# USB.net
KiCad netlist of a schematic drawn in Altium Designer
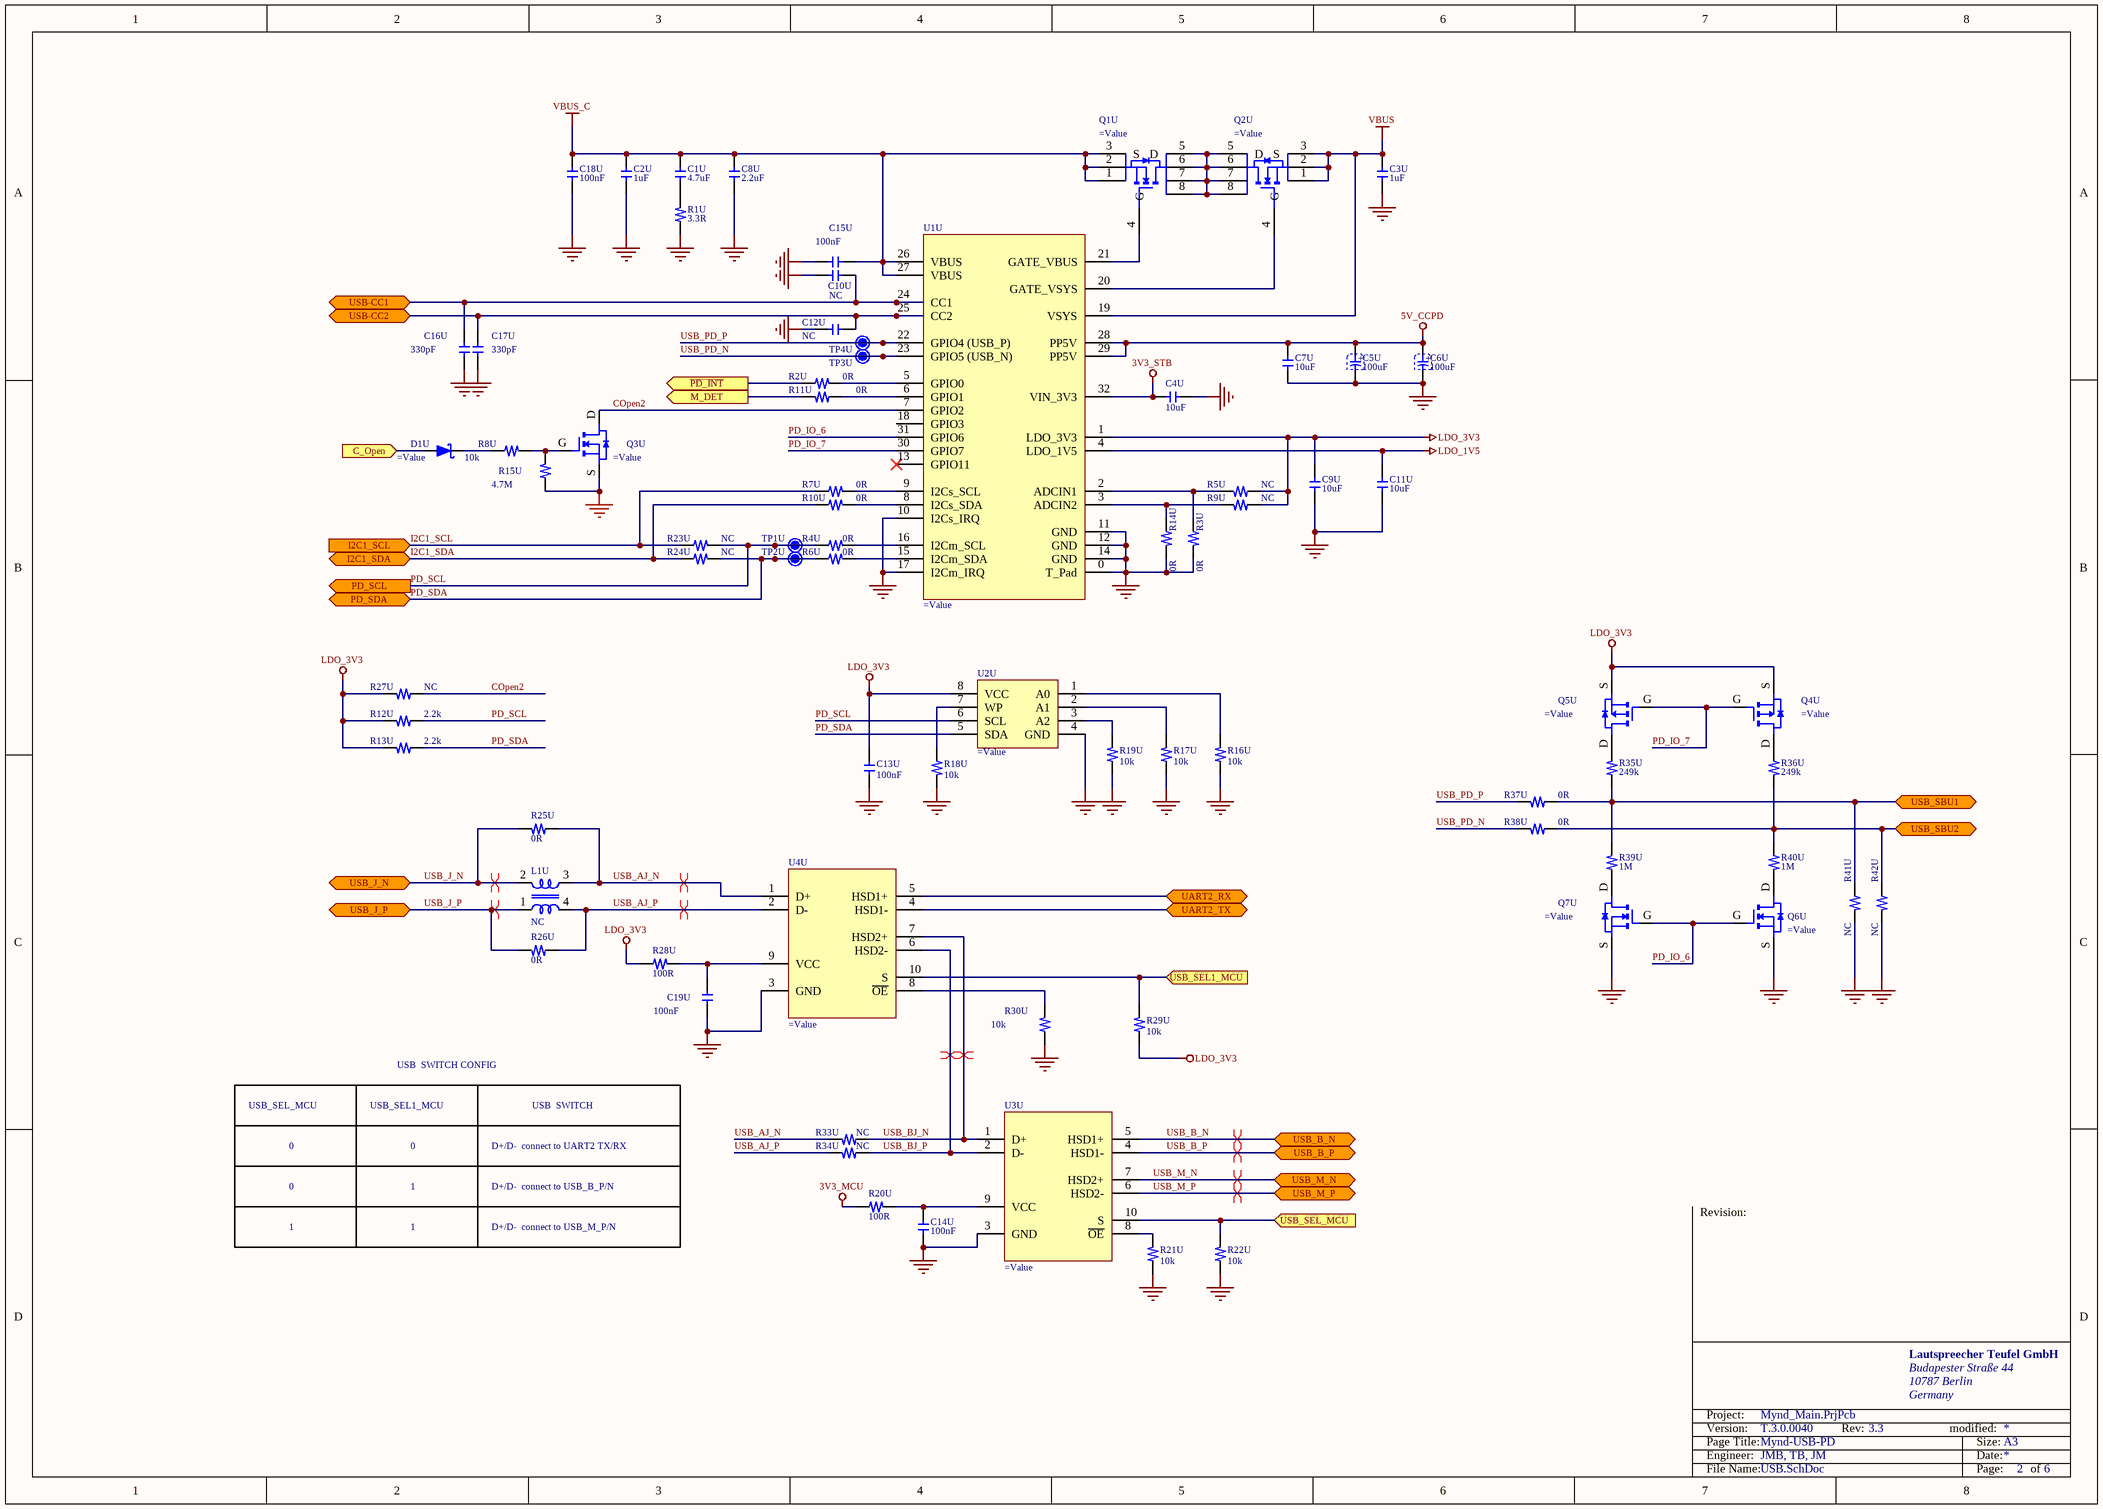
[diagram p0: USB.SchDoc]

(export (version "E")
  (design (tool "Eeschema 10.0.6"))
  (components
    (comp (ref "C1U")
      (value "4.7uF")
      (footprint "C0805_145")
      (description "PSHF SMD M CAP 4.7uF 25V ±10% 0805 X7R")
      (fields (field (name "MANUFACTURER") "Multi Sourced") (field (name "TOLERANCE") "±10%"))
      (libsource (lib "altium-import") (part "root_3_CAP1_"))
    )
    (comp (ref "C2U")
      (value "1uF")
      (footprint "C0805_145")
      (description "PSHF SMD M CAP 1uF 50V ±10% 0805 X7R")
      (fields (field (name "MANUFACTURER") "Multi Sourced") (field (name "TOLERANCE") "±10%"))
      (libsource (lib "altium-import") (part "root_3_CAP1_"))
    )
    (comp (ref "C3U")
      (value "1uF")
      (footprint "C0805_145")
      (description "PSHF SMD M CAP 1uF 50V ±10% 0805 X7R")
      (fields (field (name "MANUFACTURER") "Multi Sourced") (field (name "TOLERANCE") "±10%"))
      (libsource (lib "altium-import") (part "root_3_CAP1_"))
    )
    (comp (ref "C4U")
      (value "10uF")
      (footprint "C0805_145")
      (description "PSHF SMD M CAP 10uF 16V ±10% 0805 X7R")
      (fields (field (name "MANUFACTURER") "Multi Sourced") (field (name "TOLERANCE") "±10%"))
      (libsource (lib "altium-import") (part "root_2_CAP1_"))
    )
    (comp (ref "C5U")
      (value "100uF")
      (footprint "ECAP_SMD_630X540")
      (description "PS SMD COND ELECT 100uF 16V ±20% 105℃")
      (fields (field (name "MANUFACTURER") "Multi Sourced") (field (name "TOLERANCE") "±20%"))
      (libsource (lib "altium-import") (part "root_3_ECAP2_"))
    )
    (comp (ref "C6U")
      (value "100uF")
      (footprint "ECAP_SMD_630X540")
      (description "PS SMD COND ELECT 100uF 16V ±20% 105℃")
      (fields (field (name "MANUFACTURER") "Multi Sourced") (field (name "TOLERANCE") "±20%"))
      (libsource (lib "altium-import") (part "root_3_ECAP2_"))
    )
    (comp (ref "C7U")
      (value "10uF")
      (footprint "C0805_145")
      (description "PSHF SMD M CAP 10uF 16V ±10% 0805 X7R")
      (fields (field (name "MANUFACTURER") "Multi Sourced") (field (name "TOLERANCE") "±10%"))
      (libsource (lib "altium-import") (part "root_1_CAP1_"))
    )
    (comp (ref "C8U")
      (value "2.2uF")
      (footprint "C0805_145")
      (description "GPHF $ SMD M CAP 2.2uF 50V ±10% 0805 X5R")
      (fields (field (name "MANUFACTURER") "Multi Sourced") (field (name "TOLERANCE") "±10%"))
      (libsource (lib "altium-import") (part "root_3_CAP1_"))
    )
    (comp (ref "C9U")
      (value "10uF")
      (footprint "C0805_145")
      (description "PSHF SMD M CAP 10uF 16V ±10% 0805 X7R")
      (fields (field (name "MANUFACTURER") "Multi Sourced") (field (name "TOLERANCE") "±10%"))
      (libsource (lib "altium-import") (part "root_1_CAP1_"))
    )
    (comp (ref "C10U")
      (value "330pF")
      (footprint "C0603X80")
      (description "PSHF SMD M CAP 330pF 50V ±10% 0603 X7R")
      (fields (field (name "MANUFACTURER") "Multi Sourced") (field (name "TOLERANCE") "±10%"))
      (libsource (lib "altium-import") (part "root_2_CAP1_"))
    )
    (comp (ref "C11U")
      (value "10uF")
      (footprint "C0805_145")
      (description "PSHF SMD M CAP 10uF 16V ±10% 0805 X7R")
      (fields (field (name "MANUFACTURER") "Multi Sourced") (field (name "TOLERANCE") "±10%"))
      (libsource (lib "altium-import") (part "root_1_CAP1_"))
    )
    (comp (ref "C12U")
      (value "330pF")
      (footprint "C0603X80")
      (description "PSHF SMD M CAP 330pF 50V ±10% 0603 X7R")
      (fields (field (name "MANUFACTURER") "Multi Sourced") (field (name "TOLERANCE") "±10%"))
      (libsource (lib "altium-import") (part "root_2_CAP1_"))
    )
    (comp (ref "C13U")
      (value "100nF")
      (footprint "C0603X100")
      (description "PSHF SMD M CAP 100nF 25V ±10% 0603 X7R")
      (fields (field (name "MANUFACTURER") "Multi Sourced") (field (name "TOLERANCE") "±10%"))
      (libsource (lib "altium-import") (part "root_3_mirrored_CAP1_"))
    )
    (comp (ref "C14U")
      (value "100nF")
      (footprint "C0603X100")
      (description "PSHF SMD M CAP 100nF 25V ±10% 0603 X7R")
      (fields (field (name "MANUFACTURER") "Multi Sourced") (field (name "TOLERANCE") "±10%"))
      (libsource (lib "altium-import") (part "root_3_mirrored_CAP1_"))
    )
    (comp (ref "C15U")
      (value "100nF")
      (footprint "C0603X105")
      (description "GPHF SMD M CAP 100nF 50V ±5% 0603 X7R")
      (fields (field (name "MANUFACTURER") "Multi Sourced") (field (name "TOLERANCE") "±5%"))
      (libsource (lib "altium-import") (part "root_2_CAP1_"))
    )
    (comp (ref "C16U")
      (value "330pF")
      (footprint "C0603X80")
      (description "GPHF SMD M CAP 330pF 50V ±5% 0603 NPO")
      (fields (field (name "MANUFACTURER") "Multi Sourced") (field (name "TOLERANCE") "±5%"))
      (libsource (lib "altium-import") (part "root_3_CAP1_"))
    )
    (comp (ref "C17U")
      (value "330pF")
      (footprint "C0603X80")
      (description "GPHF SMD M CAP 330pF 50V ±5% 0603 NPO")
      (fields (field (name "MANUFACTURER") "Multi Sourced") (field (name "TOLERANCE") "±5%"))
      (libsource (lib "altium-import") (part "root_3_CAP1_"))
    )
    (comp (ref "C18U")
      (value "100nF")
      (footprint "C0603X105")
      (description "GPHF SMD M CAP 100nF 50V ±5% 0603 X7R")
      (fields (field (name "MANUFACTURER") "Multi Sourced") (field (name "TOLERANCE") "±5%"))
      (libsource (lib "altium-import") (part "root_3_CAP1_"))
    )
    (comp (ref "C19U")
      (value "100nF")
      (footprint "C0603X100")
      (description "PSHF SMD M CAP 100nF 25V ±10% 0603 X7R")
      (fields (field (name "MANUFACTURER") "Multi Sourced") (field (name "TOLERANCE") "±10%"))
      (libsource (lib "altium-import") (part "root_3_mirrored_CAP1_"))
    )
    (comp (ref "D1U")
      (value "~")
      (footprint "SOD-323")
      (description "GP SMD DIODE 2P 30V SOD323 BAT54WS PANJIT")
      (fields (field (name "MANUFACTURER") "PANJIT") (field (name "VOLTAGE") "30V"))
      (libsource (lib "altium-import") (part "root_2_mirrored_DIODE_SCHOTTKY1_"))
    )
    (comp (ref "L1U")
      (value "NC")
      (footprint "CET2012D")
      (description "COMMON MODE COIL 90Ohm 100MHz 400mA")
      (fields (field (name "MANUFACTURER") "CET CHAMPI") (field (name "PART_NUMBER") "CET2012A-900S"))
      (libsource (lib "altium-import") (part "root_2_mirrored_CET9070F-701_"))
    )
    (comp (ref "Q1U")
      (value "~")
      (footprint "DFN8_500X600X100_127_A")
      (description "PS SMD FET 8P DFN8 AP4024GEMT-HF APEC")
      (fields (field (name "MANUFACTURER") "[APEC]") (field (name "VOLTAGE") "30V"))
      (libsource (lib "altium-import") (part "root_1_mirrored_N-MOS2_8Pin_"))
    )
    (comp (ref "Q2U")
      (value "~")
      (footprint "DFN8_500X600X100_127_A")
      (description "PS SMD FET 8P DFN8 AP4024GEMT-HF APEC")
      (fields (field (name "MANUFACTURER") "[APEC]") (field (name "VOLTAGE") "30V"))
      (libsource (lib "altium-import") (part "root_1_N-MOS2_8Pin_"))
    )
    (comp (ref "Q3U")
      (value "~")
      (footprint "SOT23-GSD")
      (description "GP SMD FET 3P SOT23 2N7002K CTE")
      (fields (field (name "MANUFACTURER") "CTE") (field (name "VOLTAGE") "60V"))
      (libsource (lib "altium-import") (part "root_0_N-MOS1_"))
    )
    (comp (ref "Q4U")
      (value "~")
      (footprint "SOT23-GSD")
      (description "GPHF SMD FET 3P -30V SOT-23 CJ3401 CJ")
      (fields (field (name "MANUFACTURER") "CJ") (field (name "VOLTAGE") "-30"))
      (libsource (lib "altium-import") (part "root_2_mirrored_P-MOS1_"))
    )
    (comp (ref "Q5U")
      (value "~")
      (footprint "SOT23-GSD")
      (description "GPHF SMD FET 3P -30V SOT-23 CJ3401 CJ")
      (fields (field (name "MANUFACTURER") "CJ") (field (name "VOLTAGE") "-30"))
      (libsource (lib "altium-import") (part "root_2_P-MOS1_"))
    )
    (comp (ref "Q6U")
      (value "~")
      (footprint "SOT23_16_GSD")
      (description "GP FET 3P AO3402 SOT23 ALPHA 30V/4A")
      (fields (field (name "MANUFACTURER") "AOS") (field (name "VOLTAGE") "30V"))
      (libsource (lib "altium-import") (part "root_0_N-MOS1_"))
    )
    (comp (ref "Q7U")
      (value "~")
      (footprint "SOT23_16_GSD")
      (description "GP FET 3P AO3402 SOT23 ALPHA 30V/4A")
      (fields (field (name "MANUFACTURER") "AOS") (field (name "VOLTAGE") "30V"))
      (libsource (lib "altium-import") (part "root_0_mirrored_N-MOS1_"))
    )
    (comp (ref "R1U")
      (value "3.3R")
      (footprint "R0603")
      (description "PS SMD RES. 3.3OHM 1/10W 1% 0603")
      (fields (field (name "TOLERANCE") "1%") (field (name "MANUFACTURER") "Multi-Sourced"))
      (libsource (lib "altium-import") (part "root_1_mirrored_RES1_"))
    )
    (comp (ref "R2U")
      (value "0R")
      (footprint "R0603")
      (description "PS SMD RES. 0OHM 1/10W 5% 0603")
      (fields (field (name "TOLERANCE") "1%") (field (name "MANUFACTURER") "Multi-Sourced"))
      (libsource (lib "altium-import") (part "root_2_mirrored_RES1_"))
    )
    (comp (ref "R3U")
      (value "0R")
      (footprint "R0603")
      (description "GPHF SMD RES. 0OHM 1/10W 5% 0603")
      (fields (field (name "TOLERANCE") "5%") (field (name "MANUFACTURER") "Multi-Sourced"))
      (libsource (lib "altium-import") (part "root_3_mirrored_RES1_"))
    )
    (comp (ref "R4U")
      (value "0R")
      (footprint "R0603")
      (description "PS SMD RES. 0OHM 1/10W 5% 0603")
      (fields (field (name "TOLERANCE") "1%") (field (name "MANUFACTURER") "Multi-Sourced"))
      (libsource (lib "altium-import") (part "root_2_mirrored_RES1_"))
    )
    (comp (ref "R5U")
      (value "13k")
      (footprint "R0603")
      (description "GPHF SMD RES. 13KOHM 1/10W 1% 0603")
      (fields (field (name "TOLERANCE") "1%") (field (name "MANUFACTURER") "Multi-Sourced"))
      (libsource (lib "altium-import") (part "root_0_mirrored_RES1_"))
    )
    (comp (ref "R6U")
      (value "0R")
      (footprint "R0603")
      (description "PS SMD RES. 0OHM 1/10W 5% 0603")
      (fields (field (name "TOLERANCE") "1%") (field (name "MANUFACTURER") "Multi-Sourced"))
      (libsource (lib "altium-import") (part "root_2_mirrored_RES1_"))
    )
    (comp (ref "R7U")
      (value "0R")
      (footprint "R0603")
      (description "PS SMD RES. 0OHM 1/10W 5% 0603")
      (fields (field (name "TOLERANCE") "1%") (field (name "MANUFACTURER") "Multi-Sourced"))
      (libsource (lib "altium-import") (part "root_2_mirrored_RES1_"))
    )
    (comp (ref "R8U")
      (value "10k")
      (footprint "R0603")
      (description "GPHF SMD RES. 10KOHM 1/10W 5% 0603")
      (fields (field (name "TOLERANCE") "5%") (field (name "MANUFACTURER") "Multi-Sourced"))
      (libsource (lib "altium-import") (part "root_2_mirrored_RES1_"))
    )
    (comp (ref "R9U")
      (value "13k")
      (footprint "R0603")
      (description "GPHF SMD RES. 13KOHM 1/10W 1% 0603")
      (fields (field (name "TOLERANCE") "1%") (field (name "MANUFACTURER") "Multi-Sourced"))
      (libsource (lib "altium-import") (part "root_0_mirrored_RES1_"))
    )
    (comp (ref "R10U")
      (value "0R")
      (footprint "R0603")
      (description "PS SMD RES. 0OHM 1/10W 5% 0603")
      (fields (field (name "TOLERANCE") "1%") (field (name "MANUFACTURER") "Multi-Sourced"))
      (libsource (lib "altium-import") (part "root_2_mirrored_RES1_"))
    )
    (comp (ref "R11U")
      (value "0R")
      (footprint "R0603")
      (description "PS SMD RES. 0OHM 1/10W 5% 0603")
      (fields (field (name "TOLERANCE") "1%") (field (name "MANUFACTURER") "Multi-Sourced"))
      (libsource (lib "altium-import") (part "root_0_mirrored_RES1_"))
    )
    (comp (ref "R12U")
      (value "2.2k")
      (footprint "R0603")
      (description "PS SMD RES. 2.2KOHM 1/10W 1% 0603")
      (fields (field (name "TOLERANCE") "1%") (field (name "MANUFACTURER") "Multi-Sourced"))
      (libsource (lib "altium-import") (part "root_0_mirrored_RES1_"))
    )
    (comp (ref "R13U")
      (value "2.2k")
      (footprint "R0603")
      (description "PS SMD RES. 2.2KOHM 1/10W 1% 0603")
      (fields (field (name "TOLERANCE") "1%") (field (name "MANUFACTURER") "Multi-Sourced"))
      (libsource (lib "altium-import") (part "root_0_mirrored_RES1_"))
    )
    (comp (ref "R14U")
      (value "0R")
      (footprint "R0603")
      (description "GPHF SMD RES. 0OHM 1/10W 5% 0603")
      (fields (field (name "TOLERANCE") "5%") (field (name "MANUFACTURER") "Multi-Sourced"))
      (libsource (lib "altium-import") (part "root_3_mirrored_RES1_"))
    )
    (comp (ref "R15U")
      (value "4.7M")
      (footprint "R0603")
      (description "PS SMD RES. 4.7MOHM 1/10W 5% 0603")
      (fields (field (name "TOLERANCE") "5%") (field (name "MANUFACTURER") "Multi-Sourced"))
      (libsource (lib "altium-import") (part "root_3_RES1_"))
    )
    (comp (ref "R16U")
      (value "10k")
      (footprint "R0603")
      (description "PS SMD RES. 10KOHM 1/10W 1% 0603")
      (fields (field (name "TOLERANCE") "1%") (field (name "MANUFACTURER") "Multi-Sourced"))
      (libsource (lib "altium-import") (part "root_3_RES1_"))
    )
    (comp (ref "R17U")
      (value "10k")
      (footprint "R0603")
      (description "PS SMD RES. 10KOHM 1/10W 1% 0603")
      (fields (field (name "TOLERANCE") "1%") (field (name "MANUFACTURER") "Multi-Sourced"))
      (libsource (lib "altium-import") (part "root_3_RES1_"))
    )
    (comp (ref "R18U")
      (value "10k")
      (footprint "R0603")
      (description "PS SMD RES. 10KOHM 1/10W 1% 0603")
      (fields (field (name "TOLERANCE") "1%") (field (name "MANUFACTURER") "Multi-Sourced"))
      (libsource (lib "altium-import") (part "root_1_RES1_"))
    )
    (comp (ref "R19U")
      (value "10k")
      (footprint "R0603")
      (description "PS SMD RES. 10KOHM 1/10W 1% 0603")
      (fields (field (name "TOLERANCE") "1%") (field (name "MANUFACTURER") "Multi-Sourced"))
      (libsource (lib "altium-import") (part "root_3_RES1_"))
    )
    (comp (ref "R20U")
      (value "100R")
      (footprint "R0603")
      (description "PS SMD RES. 100OHM 1/10W 1% 0603")
      (fields (field (name "TOLERANCE") "1%") (field (name "MANUFACTURER") "Multi-Sourced"))
      (libsource (lib "altium-import") (part "root_2_mirrored_RES1_"))
    )
    (comp (ref "R21U")
      (value "10k")
      (footprint "R0603")
      (description "PS SMD RES. 10KOHM 1/10W 1% 0603")
      (fields (field (name "TOLERANCE") "1%") (field (name "MANUFACTURER") "Multi-Sourced"))
      (libsource (lib "altium-import") (part "root_1_mirrored_RES1_"))
    )
    (comp (ref "R22U")
      (value "10k")
      (footprint "R0603")
      (description "PS SMD RES. 10KOHM 1/10W 1% 0603")
      (fields (field (name "TOLERANCE") "1%") (field (name "MANUFACTURER") "Multi-Sourced"))
      (libsource (lib "altium-import") (part "root_1_mirrored_RES1_"))
    )
    (comp (ref "R23U")
      (value "0R")
      (footprint "R0603")
      (description "PS SMD RES. 0OHM 1/10W 5% 0603")
      (fields (field (name "TOLERANCE") "1%") (field (name "MANUFACTURER") "Multi-Sourced"))
      (libsource (lib "altium-import") (part "root_2_mirrored_RES1_"))
    )
    (comp (ref "R24U")
      (value "0R")
      (footprint "R0603")
      (description "PS SMD RES. 0OHM 1/10W 5% 0603")
      (fields (field (name "TOLERANCE") "1%") (field (name "MANUFACTURER") "Multi-Sourced"))
      (libsource (lib "altium-import") (part "root_2_mirrored_RES1_"))
    )
    (comp (ref "R25U")
      (value "0R")
      (footprint "R0603")
      (description "GPHF SMD RES. 0OHM 1/10W 5% 0603")
      (fields (field (name "MANUFACTURER") "Multi-Sourced") (field (name "TOLERANCE") "5%"))
      (libsource (lib "altium-import") (part "root_0_RES1_"))
    )
    (comp (ref "R26U")
      (value "0R")
      (footprint "R0603")
      (description "GPHF SMD RES. 0OHM 1/10W 5% 0603")
      (fields (field (name "MANUFACTURER") "Multi-Sourced") (field (name "TOLERANCE") "5%"))
      (libsource (lib "altium-import") (part "root_0_RES1_"))
    )
    (comp (ref "R27U")
      (value "2.2k")
      (footprint "R0603")
      (description "PS SMD RES. 2.2KOHM 1/10W 1% 0603")
      (fields (field (name "TOLERANCE") "1%") (field (name "MANUFACTURER") "Multi-Sourced"))
      (libsource (lib "altium-import") (part "root_0_mirrored_RES1_"))
    )
    (comp (ref "R28U")
      (value "100R")
      (footprint "R0603")
      (description "PS SMD RES. 100OHM 1/10W 1% 0603")
      (fields (field (name "TOLERANCE") "1%") (field (name "MANUFACTURER") "Multi-Sourced"))
      (libsource (lib "altium-import") (part "root_2_mirrored_RES1_"))
    )
    (comp (ref "R29U")
      (value "10k")
      (footprint "R0603")
      (description "PS SMD RES. 10KOHM 1/10W 1% 0603")
      (fields (field (name "TOLERANCE") "1%") (field (name "MANUFACTURER") "Multi-Sourced"))
      (libsource (lib "altium-import") (part "root_1_mirrored_RES1_"))
    )
    (comp (ref "R30U")
      (value "10k")
      (footprint "R0603")
      (description "PS SMD RES. 10KOHM 1/10W 1% 0603")
      (fields (field (name "TOLERANCE") "1%") (field (name "MANUFACTURER") "Multi-Sourced"))
      (libsource (lib "altium-import") (part "root_1_mirrored_RES1_"))
    )
    (comp (ref "R33U")
      (value "0R")
      (footprint "R0603")
      (description "GPHF SMD RES. 0OHM 1/10W 5% 0603")
      (fields (field (name "MANUFACTURER") "Multi-Sourced") (field (name "TOLERANCE") "5%"))
      (libsource (lib "altium-import") (part "root_0_RES1_"))
    )
    (comp (ref "R34U")
      (value "0R")
      (footprint "R0603")
      (description "GPHF SMD RES. 0OHM 1/10W 5% 0603")
      (fields (field (name "MANUFACTURER") "Multi-Sourced") (field (name "TOLERANCE") "5%"))
      (libsource (lib "altium-import") (part "root_0_RES1_"))
    )
    (comp (ref "R35U")
      (value "249k")
      (footprint "R0402")
      (description "GPHF SMD RES. 249KOhm 1/16W 1% 0402")
      (fields (field (name "TOLERANCE") "1%") (field (name "MANUFACTURER") "Multi-Sourced"))
      (libsource (lib "altium-import") (part "root_3_RES1_"))
    )
    (comp (ref "R36U")
      (value "249k")
      (footprint "R0402")
      (description "GPHF SMD RES. 249KOhm 1/16W 1% 0402")
      (fields (field (name "TOLERANCE") "1%") (field (name "MANUFACTURER") "Multi-Sourced"))
      (libsource (lib "altium-import") (part "root_3_mirrored_RES1_"))
    )
    (comp (ref "R37U")
      (value "0R")
      (footprint "R0603")
      (description "GPHF SMD RES. 0OHM 1/10W 5% 0603")
      (fields (field (name "MANUFACTURER") "Multi-Sourced") (field (name "TOLERANCE") "5%"))
      (libsource (lib "altium-import") (part "root_0_RES1_"))
    )
    (comp (ref "R38U")
      (value "0R")
      (footprint "R0603")
      (description "GPHF SMD RES. 0OHM 1/10W 5% 0603")
      (fields (field (name "MANUFACTURER") "Multi-Sourced") (field (name "TOLERANCE") "5%"))
      (libsource (lib "altium-import") (part "root_0_mirrored_RES1_"))
    )
    (comp (ref "R39U")
      (value "1M")
      (footprint "R0402")
      (description "GPHF SMD RES. 1MOHM 1/16W 1% 0402")
      (fields (field (name "TOLERANCE") "1%") (field (name "MANUFACTURER") "Multi-Sourced"))
      (libsource (lib "altium-import") (part "root_3_RES1_"))
    )
    (comp (ref "R40U")
      (value "1M")
      (footprint "R0402")
      (description "GPHF SMD RES. 1MOHM 1/16W 1% 0402")
      (fields (field (name "TOLERANCE") "1%") (field (name "MANUFACTURER") "Multi-Sourced"))
      (libsource (lib "altium-import") (part "root_3_mirrored_RES1_"))
    )
    (comp (ref "R41U")
      (value "0R")
      (footprint "R0603")
      (description "GPHF SMD RES. 0OHM 1/10W 5% 0603")
      (fields (field (name "MANUFACTURER") "Multi-Sourced") (field (name "TOLERANCE") "5%"))
      (libsource (lib "altium-import") (part "root_1_RES1_"))
    )
    (comp (ref "R42U")
      (value "0R")
      (footprint "R0603")
      (description "GPHF SMD RES. 0OHM 1/10W 5% 0603")
      (fields (field (name "MANUFACTURER") "Multi-Sourced") (field (name "TOLERANCE") "5%"))
      (libsource (lib "altium-import") (part "root_1_RES1_"))
    )
    (comp (ref "TP1U")
      (value "TP_T_60_40")
      (footprint "TP_T_60_40")
      (description "Test Point")
      (libsource (lib "altium-import") (part "root_0_TP_"))
    )
    (comp (ref "TP2U")
      (value "TP_T_60_40")
      (footprint "TP_T_60_40")
      (description "Test Point")
      (libsource (lib "altium-import") (part "root_0_TP_"))
    )
    (comp (ref "TP3U")
      (value "TP06")
      (footprint "TP060")
      (description "Test Point")
      (libsource (lib "altium-import") (part "root_2_TP_"))
    )
    (comp (ref "TP4U")
      (value "TP06")
      (footprint "TP060")
      (description "Test Point")
      (libsource (lib "altium-import") (part "root_2_TP_"))
    )
    (comp (ref "U1U")
      (value "~")
      (footprint "QFN32_400X400X80_40_P280X280_A")
      (description "SMD IC 32P VQFN PTPS25751SRSMR TI")
      (fields (field (name "MANUFACTURER") "TI") (field (name "PART_NUMBER") "PTPS25751SRSMR"))
      (libsource (lib "altium-import") (part "root_0_TPS25750S_"))
    )
    (comp (ref "U2U")
      (value "~")
      (footprint "SO-8")
      (description "SMD IC 8P SOP8 FT24C512A-TSR-T")
      (fields (field (name "MANUFACTURER") "HUIMANG") (field (name "PART_NUMBER") "FT24C512A-TSR-T"))
      (libsource (lib "altium-import") (part "root_0_mirrored_24CXX_"))
    )
    (comp (ref "U3U")
      (value "~")
      (footprint "QFN10_180X140X60_40")
      (description "GS SMD IC 10P UTQFN SGM7227YUWQ10G SGMICRO")
      (fields (field (name "MANUFACTURER") "[SGMICRO]") (field (name "PART_NUMBER") "SGM7227YUWQ10G"))
      (libsource (lib "altium-import") (part "root_0_SGM7227_QFN_"))
    )
    (comp (ref "U4U")
      (value "~")
      (footprint "QFN10_180X140X60_40")
      (description "GS SMD IC 10P UTQFN SGM7227YUWQ10G SGMICRO")
      (fields (field (name "MANUFACTURER") "[SGMICRO]") (field (name "PART_NUMBER") "SGM7227YUWQ10G"))
      (libsource (lib "altium-import") (part "root_0_SGM7227_QFN_"))
    )
  )
  (nets
    (net (code "1") (name "/COpen2") (class "Default")
      (node (ref "Q3U") (pin "D") (pinfunction "D_D") (pintype "passive"))
      (node (ref "R27U") (pin "1") (pinfunction "1_1") (pintype "passive"))
      (node (ref "U1U") (pin "7") (pinfunction "GPIO2_7") (pintype "passive"))
    )
    (net (code "2") (name "/C_Open") (class "Default")
      (node (ref "D1U") (pin "A") (pinfunction "A_A") (pintype "passive"))
    )
    (net (code "3") (name "/I2C1_SCL") (class "Default")
      (node (ref "R23U") (pin "1") (pinfunction "1_1") (pintype "passive"))
      (node (ref "R7U") (pin "1") (pinfunction "1_1") (pintype "passive"))
    )
    (net (code "4") (name "/I2C1_SDA") (class "Default")
      (node (ref "R10U") (pin "1") (pinfunction "1_1") (pintype "passive"))
      (node (ref "R24U") (pin "1") (pinfunction "1_1") (pintype "passive"))
    )
    (net (code "5") (name "/M_DET") (class "Default")
      (node (ref "R11U") (pin "2") (pinfunction "2_2") (pintype "passive"))
    )
    (net (code "6") (name "/PD_INT") (class "Default")
      (node (ref "R2U") (pin "1") (pinfunction "1_1") (pintype "passive"))
    )
    (net (code "7") (name "/PD_IO_6") (class "Default")
      (node (ref "Q6U") (pin "G") (pinfunction "G_G") (pintype "passive"))
      (node (ref "Q7U") (pin "G") (pinfunction "G_G") (pintype "passive"))
      (node (ref "U1U") (pin "31") (pinfunction "GPIO6_31") (pintype "passive"))
    )
    (net (code "8") (name "/PD_IO_7") (class "Default")
      (node (ref "Q4U") (pin "G") (pinfunction "G_G") (pintype "passive"))
      (node (ref "Q5U") (pin "G") (pinfunction "G_G") (pintype "passive"))
      (node (ref "U1U") (pin "30") (pinfunction "GPIO7_30") (pintype "passive"))
    )
    (net (code "9") (name "/PD_SCL") (class "Default")
      (node (ref "R12U") (pin "1") (pinfunction "1_1") (pintype "passive"))
      (node (ref "R23U") (pin "2") (pinfunction "2_2") (pintype "passive"))
      (node (ref "R4U") (pin "1") (pinfunction "1_1") (pintype "passive"))
      (node (ref "TP1U") (pin "1") (pinfunction "1_1") (pintype "passive"))
      (node (ref "U2U") (pin "6") (pinfunction "SCL_6") (pintype "passive"))
    )
    (net (code "10") (name "/PD_SDA") (class "Default")
      (node (ref "R13U") (pin "1") (pinfunction "1_1") (pintype "passive"))
      (node (ref "R24U") (pin "2") (pinfunction "2_2") (pintype "passive"))
      (node (ref "R6U") (pin "1") (pinfunction "1_1") (pintype "passive"))
      (node (ref "TP2U") (pin "1") (pinfunction "1_1") (pintype "passive"))
      (node (ref "U2U") (pin "5") (pinfunction "SDA_5") (pintype "passive"))
    )
    (net (code "11") (name "/UART2_RX") (class "Default")
      (node (ref "U4U") (pin "5") (pinfunction "HSD1+_5") (pintype "passive"))
    )
    (net (code "12") (name "/UART2_TX") (class "Default")
      (node (ref "U4U") (pin "4") (pinfunction "HSD1-_4") (pintype "passive"))
    )
    (net (code "13") (name "/USB-CC1") (class "Default")
      (node (ref "C10U") (pin "1") (pinfunction "1_1") (pintype "passive"))
      (node (ref "C16U") (pin "1") (pinfunction "1_1") (pintype "passive"))
      (node (ref "U1U") (pin "24") (pinfunction "CC1_24") (pintype "passive"))
    )
    (net (code "14") (name "/USB-CC2") (class "Default")
      (node (ref "C12U") (pin "1") (pinfunction "1_1") (pintype "passive"))
      (node (ref "C17U") (pin "1") (pinfunction "1_1") (pintype "passive"))
      (node (ref "U1U") (pin "25") (pinfunction "CC2_25") (pintype "passive"))
    )
    (net (code "15") (name "/USB_AJ_N") (class "Default")
      (node (ref "L1U") (pin "3") (pinfunction "3_3") (pintype "passive"))
      (node (ref "R25U") (pin "2") (pinfunction "2_2") (pintype "passive"))
      (node (ref "R33U") (pin "1") (pinfunction "1_1") (pintype "passive"))
      (node (ref "U4U") (pin "1") (pinfunction "D+_1") (pintype "passive"))
    )
    (net (code "16") (name "/USB_AJ_P") (class "Default")
      (node (ref "L1U") (pin "4") (pinfunction "4_4") (pintype "passive"))
      (node (ref "R26U") (pin "2") (pinfunction "2_2") (pintype "passive"))
      (node (ref "R34U") (pin "1") (pinfunction "1_1") (pintype "passive"))
      (node (ref "U4U") (pin "2") (pinfunction "D-_2") (pintype "passive"))
    )
    (net (code "17") (name "/USB_BJ_N") (class "Default")
      (node (ref "R33U") (pin "2") (pinfunction "2_2") (pintype "passive"))
      (node (ref "U3U") (pin "1") (pinfunction "D+_1") (pintype "passive"))
      (node (ref "U4U") (pin "7") (pinfunction "HSD2+_7") (pintype "passive"))
    )
    (net (code "18") (name "/USB_BJ_P") (class "Default")
      (node (ref "R34U") (pin "2") (pinfunction "2_2") (pintype "passive"))
      (node (ref "U3U") (pin "2") (pinfunction "D-_2") (pintype "passive"))
      (node (ref "U4U") (pin "6") (pinfunction "HSD2-_6") (pintype "passive"))
    )
    (net (code "19") (name "/USB_B_N") (class "Default")
      (node (ref "U3U") (pin "5") (pinfunction "HSD1+_5") (pintype "passive"))
    )
    (net (code "20") (name "/USB_B_P") (class "Default")
      (node (ref "U3U") (pin "4") (pinfunction "HSD1-_4") (pintype "passive"))
    )
    (net (code "21") (name "/USB_J_N") (class "Default")
      (node (ref "L1U") (pin "2") (pinfunction "2_2") (pintype "passive"))
      (node (ref "R25U") (pin "1") (pinfunction "1_1") (pintype "passive"))
    )
    (net (code "22") (name "/USB_J_P") (class "Default")
      (node (ref "L1U") (pin "1") (pinfunction "1_1") (pintype "passive"))
      (node (ref "R26U") (pin "1") (pinfunction "1_1") (pintype "passive"))
    )
    (net (code "23") (name "/USB_M_N") (class "Default")
      (node (ref "U3U") (pin "7") (pinfunction "HSD2+_7") (pintype "passive"))
    )
    (net (code "24") (name "/USB_M_P") (class "Default")
      (node (ref "U3U") (pin "6") (pinfunction "HSD2-_6") (pintype "passive"))
    )
    (net (code "25") (name "/USB_PD_N") (class "Default")
      (node (ref "R38U") (pin "2") (pinfunction "2_2") (pintype "passive"))
      (node (ref "TP3U") (pin "1") (pinfunction "1_1") (pintype "passive"))
      (node (ref "U1U") (pin "23") (pinfunction "GPIO5_(USB_N)_23") (pintype "passive"))
    )
    (net (code "26") (name "/USB_PD_P") (class "Default")
      (node (ref "R37U") (pin "1") (pinfunction "1_1") (pintype "passive"))
      (node (ref "TP4U") (pin "1") (pinfunction "1_1") (pintype "passive"))
      (node (ref "U1U") (pin "22") (pinfunction "GPIO4_(USB_P)_22") (pintype "passive"))
    )
    (net (code "27") (name "/USB_SBU1") (class "Default")
      (node (ref "R35U") (pin "2") (pinfunction "2_2") (pintype "passive"))
      (node (ref "R37U") (pin "2") (pinfunction "2_2") (pintype "passive"))
      (node (ref "R39U") (pin "1") (pinfunction "1_1") (pintype "passive"))
      (node (ref "R41U") (pin "2") (pinfunction "2_2") (pintype "passive"))
    )
    (net (code "28") (name "/USB_SBU2") (class "Default")
      (node (ref "R36U") (pin "2") (pinfunction "2_2") (pintype "passive"))
      (node (ref "R38U") (pin "1") (pinfunction "1_1") (pintype "passive"))
      (node (ref "R40U") (pin "1") (pinfunction "1_1") (pintype "passive"))
      (node (ref "R42U") (pin "2") (pinfunction "2_2") (pintype "passive"))
    )
    (net (code "29") (name "/USB_SEL1_MCU") (class "Default")
      (node (ref "R29U") (pin "2") (pinfunction "2_2") (pintype "passive"))
      (node (ref "U4U") (pin "10") (pinfunction "S_10") (pintype "passive"))
    )
    (net (code "30") (name "/USB_SEL_MCU") (class "Default")
      (node (ref "R22U") (pin "2") (pinfunction "2_2") (pintype "passive"))
      (node (ref "U3U") (pin "10") (pinfunction "S_10") (pintype "passive"))
    )
    (net (code "31") (name "3V3_MCU") (class "Default")
      (node (ref "R20U") (pin "1") (pinfunction "1_1") (pintype "passive"))
    )
    (net (code "32") (name "3V3_STB") (class "Default")
      (node (ref "C4U") (pin "2") (pinfunction "2_2") (pintype "passive"))
      (node (ref "U1U") (pin "32") (pinfunction "VIN_3V3_32") (pintype "passive"))
    )
    (net (code "33") (name "5V_CCPD") (class "Default")
      (node (ref "C5U") (pin "1") (pinfunction "1_1") (pintype "passive"))
      (node (ref "C6U") (pin "1") (pinfunction "1_1") (pintype "passive"))
      (node (ref "C7U") (pin "2") (pinfunction "2_2") (pintype "passive"))
      (node (ref "U1U") (pin "28") (pinfunction "PP5V_28") (pintype "passive"))
      (node (ref "U1U") (pin "29") (pinfunction "PP5V_29") (pintype "passive"))
    )
    (net (code "34") (name "GND") (class "Default")
      (node (ref "C10U") (pin "2") (pinfunction "2_2") (pintype "passive"))
      (node (ref "C11U") (pin "1") (pinfunction "1_1") (pintype "passive"))
      (node (ref "C12U") (pin "2") (pinfunction "2_2") (pintype "passive"))
      (node (ref "C13U") (pin "2") (pinfunction "2_2") (pintype "passive"))
      (node (ref "C14U") (pin "2") (pinfunction "2_2") (pintype "passive"))
      (node (ref "C15U") (pin "2") (pinfunction "2_2") (pintype "passive"))
      (node (ref "C16U") (pin "2") (pinfunction "2_2") (pintype "passive"))
      (node (ref "C17U") (pin "2") (pinfunction "2_2") (pintype "passive"))
      (node (ref "C18U") (pin "2") (pinfunction "2_2") (pintype "passive"))
      (node (ref "C19U") (pin "2") (pinfunction "2_2") (pintype "passive"))
      (node (ref "C2U") (pin "2") (pinfunction "2_2") (pintype "passive"))
      (node (ref "C3U") (pin "2") (pinfunction "2_2") (pintype "passive"))
      (node (ref "C4U") (pin "1") (pinfunction "1_1") (pintype "passive"))
      (node (ref "C5U") (pin "2") (pinfunction "2_2") (pintype "passive"))
      (node (ref "C6U") (pin "2") (pinfunction "2_2") (pintype "passive"))
      (node (ref "C7U") (pin "1") (pinfunction "1_1") (pintype "passive"))
      (node (ref "C8U") (pin "2") (pinfunction "2_2") (pintype "passive"))
      (node (ref "C9U") (pin "1") (pinfunction "1_1") (pintype "passive"))
      (node (ref "Q3U") (pin "S") (pinfunction "S_S") (pintype "passive"))
      (node (ref "Q6U") (pin "S") (pinfunction "S_S") (pintype "passive"))
      (node (ref "Q7U") (pin "S") (pinfunction "S_S") (pintype "passive"))
      (node (ref "R14U") (pin "2") (pinfunction "2_2") (pintype "passive"))
      (node (ref "R15U") (pin "2") (pinfunction "2_2") (pintype "passive"))
      (node (ref "R16U") (pin "2") (pinfunction "2_2") (pintype "passive"))
      (node (ref "R17U") (pin "2") (pinfunction "2_2") (pintype "passive"))
      (node (ref "R18U") (pin "1") (pinfunction "1_1") (pintype "passive"))
      (node (ref "R19U") (pin "2") (pinfunction "2_2") (pintype "passive"))
      (node (ref "R1U") (pin "1") (pinfunction "1_1") (pintype "passive"))
      (node (ref "R21U") (pin "1") (pinfunction "1_1") (pintype "passive"))
      (node (ref "R22U") (pin "1") (pinfunction "1_1") (pintype "passive"))
      (node (ref "R30U") (pin "1") (pinfunction "1_1") (pintype "passive"))
      (node (ref "R3U") (pin "2") (pinfunction "2_2") (pintype "passive"))
      (node (ref "R41U") (pin "1") (pinfunction "1_1") (pintype "passive"))
      (node (ref "R42U") (pin "1") (pinfunction "1_1") (pintype "passive"))
      (node (ref "U1U") (pin "0") (pinfunction "T_Pad_0") (pintype "passive"))
      (node (ref "U1U") (pin "10") (pinfunction "I2Cs_IRQ_10") (pintype "passive"))
      (node (ref "U1U") (pin "11") (pinfunction "GND_11") (pintype "passive"))
      (node (ref "U1U") (pin "12") (pinfunction "GND_12") (pintype "passive"))
      (node (ref "U1U") (pin "14") (pinfunction "GND_14") (pintype "passive"))
      (node (ref "U1U") (pin "17") (pinfunction "I2Cm_IRQ_17") (pintype "passive"))
      (node (ref "U2U") (pin "4") (pinfunction "GND_4") (pintype "passive"))
      (node (ref "U3U") (pin "3") (pinfunction "GND_3") (pintype "passive"))
      (node (ref "U4U") (pin "3") (pinfunction "GND_3") (pintype "passive"))
    )
    (net (code "35") (name "LDO_1V5") (class "Default")
      (node (ref "C11U") (pin "2") (pinfunction "2_2") (pintype "passive"))
      (node (ref "U1U") (pin "4") (pinfunction "LDO_1V5_4") (pintype "passive"))
    )
    (net (code "36") (name "LDO_3V3") (class "Default")
      (node (ref "C13U") (pin "1") (pinfunction "1_1") (pintype "passive"))
      (node (ref "C9U") (pin "2") (pinfunction "2_2") (pintype "passive"))
      (node (ref "Q4U") (pin "S") (pinfunction "S_S") (pintype "passive"))
      (node (ref "Q5U") (pin "S") (pinfunction "S_S") (pintype "passive"))
      (node (ref "R12U") (pin "2") (pinfunction "2_2") (pintype "passive"))
      (node (ref "R13U") (pin "2") (pinfunction "2_2") (pintype "passive"))
      (node (ref "R27U") (pin "2") (pinfunction "2_2") (pintype "passive"))
      (node (ref "R28U") (pin "1") (pinfunction "1_1") (pintype "passive"))
      (node (ref "R29U") (pin "1") (pinfunction "1_1") (pintype "passive"))
      (node (ref "R5U") (pin "1") (pinfunction "1_1") (pintype "passive"))
      (node (ref "R9U") (pin "1") (pinfunction "1_1") (pintype "passive"))
      (node (ref "U1U") (pin "1") (pinfunction "LDO_3V3_1") (pintype "passive"))
      (node (ref "U2U") (pin "8") (pinfunction "VCC_8") (pintype "passive"))
    )
    (net (code "37") (name "Net-(C1U-Pad2)") (class "Default")
      (node (ref "C1U") (pin "2") (pinfunction "2_2") (pintype "passive"))
      (node (ref "R1U") (pin "2") (pinfunction "2_2") (pintype "passive"))
    )
    (net (code "38") (name "Net-(D1U-PadK)") (class "Default")
      (node (ref "D1U") (pin "K") (pinfunction "K_K") (pintype "passive"))
      (node (ref "R8U") (pin "1") (pinfunction "1_1") (pintype "passive"))
    )
    (net (code "39") (name "Net-(Q1U-D-Pad5)") (class "Default")
      (node (ref "Q1U") (pin "5") (pinfunction "D_5") (pintype "passive"))
      (node (ref "Q1U") (pin "6") (pinfunction "D_6") (pintype "passive"))
      (node (ref "Q1U") (pin "7") (pinfunction "D_7") (pintype "passive"))
      (node (ref "Q1U") (pin "8") (pinfunction "D_8") (pintype "passive"))
      (node (ref "Q2U") (pin "5") (pinfunction "D_5") (pintype "passive"))
      (node (ref "Q2U") (pin "6") (pinfunction "D_6") (pintype "passive"))
      (node (ref "Q2U") (pin "7") (pinfunction "D_7") (pintype "passive"))
      (node (ref "Q2U") (pin "8") (pinfunction "D_8") (pintype "passive"))
    )
    (net (code "40") (name "Net-(Q1U-G)") (class "Default")
      (node (ref "Q1U") (pin "4") (pinfunction "G_4") (pintype "passive"))
      (node (ref "U1U") (pin "21") (pinfunction "GATE_VBUS_21") (pintype "passive"))
    )
    (net (code "41") (name "Net-(Q2U-G)") (class "Default")
      (node (ref "Q2U") (pin "4") (pinfunction "G_4") (pintype "passive"))
      (node (ref "U1U") (pin "20") (pinfunction "GATE_VSYS_20") (pintype "passive"))
    )
    (net (code "42") (name "Net-(Q3U-PadG)") (class "Default")
      (node (ref "Q3U") (pin "G") (pinfunction "G_G") (pintype "passive"))
      (node (ref "R15U") (pin "1") (pinfunction "1_1") (pintype "passive"))
      (node (ref "R8U") (pin "2") (pinfunction "2_2") (pintype "passive"))
    )
    (net (code "43") (name "Net-(Q4U-PadD)") (class "Default")
      (node (ref "Q4U") (pin "D") (pinfunction "D_D") (pintype "passive"))
      (node (ref "R36U") (pin "1") (pinfunction "1_1") (pintype "passive"))
    )
    (net (code "44") (name "Net-(Q5U-PadD)") (class "Default")
      (node (ref "Q5U") (pin "D") (pinfunction "D_D") (pintype "passive"))
      (node (ref "R35U") (pin "1") (pinfunction "1_1") (pintype "passive"))
    )
    (net (code "45") (name "Net-(Q6U-PadD)") (class "Default")
      (node (ref "Q6U") (pin "D") (pinfunction "D_D") (pintype "passive"))
      (node (ref "R40U") (pin "2") (pinfunction "2_2") (pintype "passive"))
    )
    (net (code "46") (name "Net-(Q7U-PadD)") (class "Default")
      (node (ref "Q7U") (pin "D") (pinfunction "D_D") (pintype "passive"))
      (node (ref "R39U") (pin "2") (pinfunction "2_2") (pintype "passive"))
    )
    (net (code "47") (name "Net-(U1U-ADCIN1)") (class "Default")
      (node (ref "R3U") (pin "1") (pinfunction "1_1") (pintype "passive"))
      (node (ref "R5U") (pin "2") (pinfunction "2_2") (pintype "passive"))
      (node (ref "U1U") (pin "2") (pinfunction "ADCIN1_2") (pintype "passive"))
    )
    (net (code "48") (name "Net-(U1U-ADCIN2)") (class "Default")
      (node (ref "R14U") (pin "1") (pinfunction "1_1") (pintype "passive"))
      (node (ref "R9U") (pin "2") (pinfunction "2_2") (pintype "passive"))
      (node (ref "U1U") (pin "3") (pinfunction "ADCIN2_3") (pintype "passive"))
    )
    (net (code "49") (name "Net-(U1U-GPIO0)") (class "Default")
      (node (ref "R2U") (pin "2") (pinfunction "2_2") (pintype "passive"))
      (node (ref "U1U") (pin "5") (pinfunction "GPIO0_5") (pintype "passive"))
    )
    (net (code "50") (name "Net-(U1U-GPIO1)") (class "Default")
      (node (ref "R11U") (pin "1") (pinfunction "1_1") (pintype "passive"))
      (node (ref "U1U") (pin "6") (pinfunction "GPIO1_6") (pintype "passive"))
    )
    (net (code "51") (name "Net-(U1U-I2Cm_SCL)") (class "Default")
      (node (ref "R4U") (pin "2") (pinfunction "2_2") (pintype "passive"))
      (node (ref "U1U") (pin "16") (pinfunction "I2Cm_SCL_16") (pintype "passive"))
    )
    (net (code "52") (name "Net-(U1U-I2Cm_SDA)") (class "Default")
      (node (ref "R6U") (pin "2") (pinfunction "2_2") (pintype "passive"))
      (node (ref "U1U") (pin "15") (pinfunction "I2Cm_SDA_15") (pintype "passive"))
    )
    (net (code "53") (name "Net-(U1U-I2Cs_SCL)") (class "Default")
      (node (ref "R7U") (pin "2") (pinfunction "2_2") (pintype "passive"))
      (node (ref "U1U") (pin "9") (pinfunction "I2Cs_SCL_9") (pintype "passive"))
    )
    (net (code "54") (name "Net-(U1U-I2Cs_SDA)") (class "Default")
      (node (ref "R10U") (pin "2") (pinfunction "2_2") (pintype "passive"))
      (node (ref "U1U") (pin "8") (pinfunction "I2Cs_SDA_8") (pintype "passive"))
    )
    (net (code "55") (name "Net-(U2U-A0)") (class "Default")
      (node (ref "R16U") (pin "1") (pinfunction "1_1") (pintype "passive"))
      (node (ref "U2U") (pin "1") (pinfunction "A0_1") (pintype "passive"))
    )
    (net (code "56") (name "Net-(U2U-A1)") (class "Default")
      (node (ref "R17U") (pin "1") (pinfunction "1_1") (pintype "passive"))
      (node (ref "U2U") (pin "2") (pinfunction "A1_2") (pintype "passive"))
    )
    (net (code "57") (name "Net-(U2U-A2)") (class "Default")
      (node (ref "R19U") (pin "1") (pinfunction "1_1") (pintype "passive"))
      (node (ref "U2U") (pin "3") (pinfunction "A2_3") (pintype "passive"))
    )
    (net (code "58") (name "Net-(U2U-WP)") (class "Default")
      (node (ref "R18U") (pin "2") (pinfunction "2_2") (pintype "passive"))
      (node (ref "U2U") (pin "7") (pinfunction "WP_7") (pintype "passive"))
    )
    (net (code "59") (name "Net-(U3U-VCC)") (class "Default")
      (node (ref "C14U") (pin "1") (pinfunction "1_1") (pintype "passive"))
      (node (ref "R20U") (pin "2") (pinfunction "2_2") (pintype "passive"))
      (node (ref "U3U") (pin "9") (pinfunction "VCC_9") (pintype "passive"))
    )
    (net (code "60") (name "Net-(U3U-~{OE})") (class "Default")
      (node (ref "R21U") (pin "2") (pinfunction "2_2") (pintype "passive"))
      (node (ref "U3U") (pin "8") (pinfunction "~{OE}_8") (pintype "passive"))
    )
    (net (code "61") (name "Net-(U4U-VCC)") (class "Default")
      (node (ref "C19U") (pin "1") (pinfunction "1_1") (pintype "passive"))
      (node (ref "R28U") (pin "2") (pinfunction "2_2") (pintype "passive"))
      (node (ref "U4U") (pin "9") (pinfunction "VCC_9") (pintype "passive"))
    )
    (net (code "62") (name "Net-(U4U-~{OE})") (class "Default")
      (node (ref "R30U") (pin "2") (pinfunction "2_2") (pintype "passive"))
      (node (ref "U4U") (pin "8") (pinfunction "~{OE}_8") (pintype "passive"))
    )
    (net (code "63") (name "VBUS") (class "Default")
      (node (ref "C3U") (pin "1") (pinfunction "1_1") (pintype "passive"))
      (node (ref "Q2U") (pin "1") (pinfunction "S_1") (pintype "passive"))
      (node (ref "Q2U") (pin "2") (pinfunction "S_2") (pintype "passive"))
      (node (ref "Q2U") (pin "3") (pinfunction "S_3") (pintype "passive"))
      (node (ref "U1U") (pin "19") (pinfunction "VSYS_19") (pintype "passive"))
    )
    (net (code "64") (name "VBUS_C") (class "Default")
      (node (ref "C15U") (pin "1") (pinfunction "1_1") (pintype "passive"))
      (node (ref "C18U") (pin "1") (pinfunction "1_1") (pintype "passive"))
      (node (ref "C1U") (pin "1") (pinfunction "1_1") (pintype "passive"))
      (node (ref "C2U") (pin "1") (pinfunction "1_1") (pintype "passive"))
      (node (ref "C8U") (pin "1") (pinfunction "1_1") (pintype "passive"))
      (node (ref "Q1U") (pin "1") (pinfunction "S_1") (pintype "passive"))
      (node (ref "Q1U") (pin "2") (pinfunction "S_2") (pintype "passive"))
      (node (ref "Q1U") (pin "3") (pinfunction "S_3") (pintype "passive"))
      (node (ref "U1U") (pin "26") (pinfunction "VBUS_26") (pintype "passive"))
      (node (ref "U1U") (pin "27") (pinfunction "VBUS_27") (pintype "passive"))
    )
    (net (code "65") (name "unconnected-(U1U-GPIO3-Pad18)") (class "Default")
      (node (ref "U1U") (pin "18") (pinfunction "GPIO3_18") (pintype "passive"))
    )
    (net (code "66") (name "unconnected-(U1U-GPIO11-Pad13)") (class "Default")
      (node (ref "U1U") (pin "13") (pinfunction "GPIO11_13") (pintype "passive+no_connect"))
    )
  )
)
